# RF_Antenna.net
KiCad netlist of a schematic drawn in Altium Designer
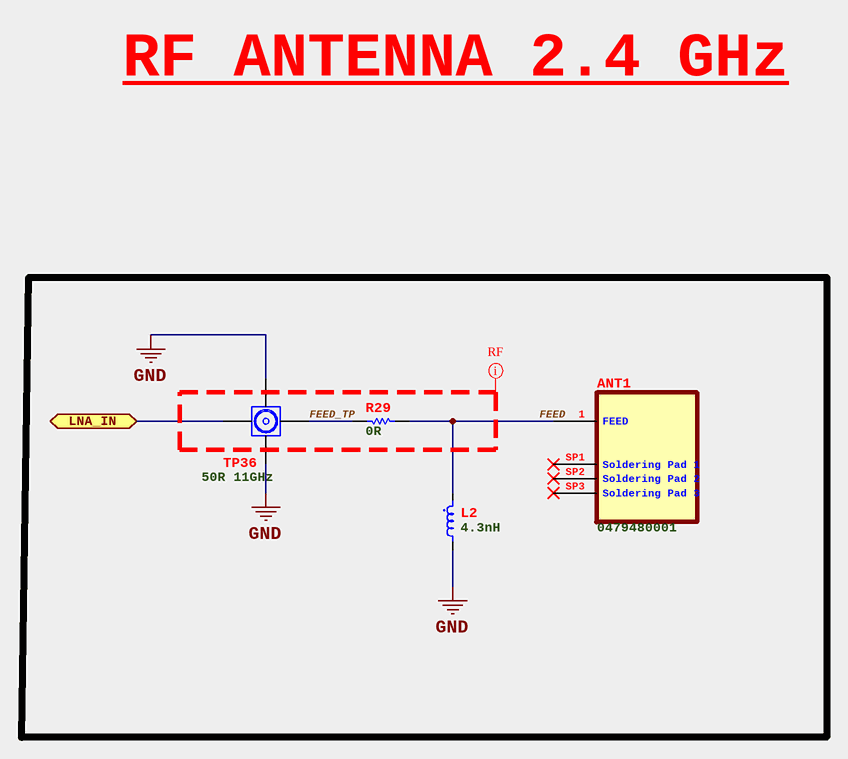
[diagram p0: RF Antenna.SchDoc]

(export (version "E")
  (design (tool "Eeschema 10.0.6"))
  (components
    (comp (ref "ANT1")
      (value "0479480001")
      (footprint "ANT_MOLEX_0479480001")
      (description "2.4GHz Bluetooth, WLAN, Zigbee™ Chip RF Antenna 2.4GHz ~ 2.483.5GHz 3dBi Solder Surface Mount")
      (fields (field (name "MANUFACTURER") "Molex"))
      (libsource (lib "Cellar Watchdog") (part "ANT_0479480001"))
    )
    (comp (ref "L2")
      (value "4.3nH")
      (footprint "IND_0402")
      (description "4.3 nH Unshielded Multilayer Inductor 750 mA 140mOhm Max 0402 (1005 Metric)")
      (fields
        (field (name "MANUFACTURER") "Murata")
        (field (name "MANUFACTURER PART NUMBER") "LQG15HS4N3B02D")
      )
      (libsource (lib "Cellar Watchdog") (part "IND_4.3nH-750mA-2%_0402"))
    )
    (comp (ref "R29")
      (value "0R")
      (footprint "RES_0603")
      (description "0 Ohms Jumper Chip Resistor 0603 (1608 Metric) Moisture Resistant Thick Film")
      (fields
        (field (name "MANUFACTURER") "Yageo")
        (field (name "MANUFACTURER PART NUMBER") "RC0603FR-070RL")
      )
      (libsource (lib "Cellar Watchdog") (part "RES_0R-100mW-1%_0603"))
    )
    (comp (ref "TP36")
      (value "50R 11GHz")
      (footprint "CON-RCPT_U.FL_MM8030-2610RJ3")
      (description "SWG Connector Receptacle, Female Socket 50Ohm Surface Mount Solder")
      (fields
        (field (name "MANUFACTURER") "Murata")
        (field (name "MANUFACTURER PART NUMBER") "MM8030-2610RJ3")
      )
      (libsource (lib "Cellar Watchdog") (part "CON-RCPT_U.FL-MM8030-2610RJ3"))
    )
  )
  (nets
    (net (code "1") (name "/FEED") (class "Default")
      (node (ref "ANT1") (pin "1") (pinfunction "FEED_1") (pintype "passive"))
      (node (ref "L2") (pin "1") (pinfunction "1_1") (pintype "passive"))
      (node (ref "R29") (pin "1") (pinfunction "1_1") (pintype "passive"))
    )
    (net (code "2") (name "/FEED_TP") (class "Default")
      (node (ref "R29") (pin "2") (pinfunction "2_2") (pintype "passive"))
      (node (ref "TP36") (pin "1") (pinfunction "IN_1") (pintype "passive"))
    )
    (net (code "3") (name "/LNA_IN") (class "Default")
      (node (ref "TP36") (pin "2") (pinfunction "OUT_2") (pintype "passive"))
    )
    (net (code "4") (name "GND") (class "Default")
      (node (ref "L2") (pin "2") (pinfunction "2_2") (pintype "passive"))
      (node (ref "TP36") (pin "3") (pinfunction "GND_3") (pintype "power_in"))
      (node (ref "TP36") (pin "4") (pinfunction "GND_4") (pintype "power_in"))
    )
    (net (code "5") (name "unconnected-(ANT1-Soldering_Pad_1-PadSP1)") (class "Default")
      (node (ref "ANT1") (pin "SP1") (pinfunction "Soldering_Pad_1_SP1") (pintype "passive+no_connect"))
    )
    (net (code "6") (name "unconnected-(ANT1-Soldering_Pad_2-PadSP2)") (class "Default")
      (node (ref "ANT1") (pin "SP2") (pinfunction "Soldering_Pad_2_SP2") (pintype "passive+no_connect"))
    )
    (net (code "7") (name "unconnected-(ANT1-Soldering_Pad_3-PadSP3)") (class "Default")
      (node (ref "ANT1") (pin "SP3") (pinfunction "Soldering_Pad_3_SP3") (pintype "passive+no_connect"))
    )
  )
)
